# geekworm-monitor.net
KiCad netlist of a schematic drawn in EAGLE
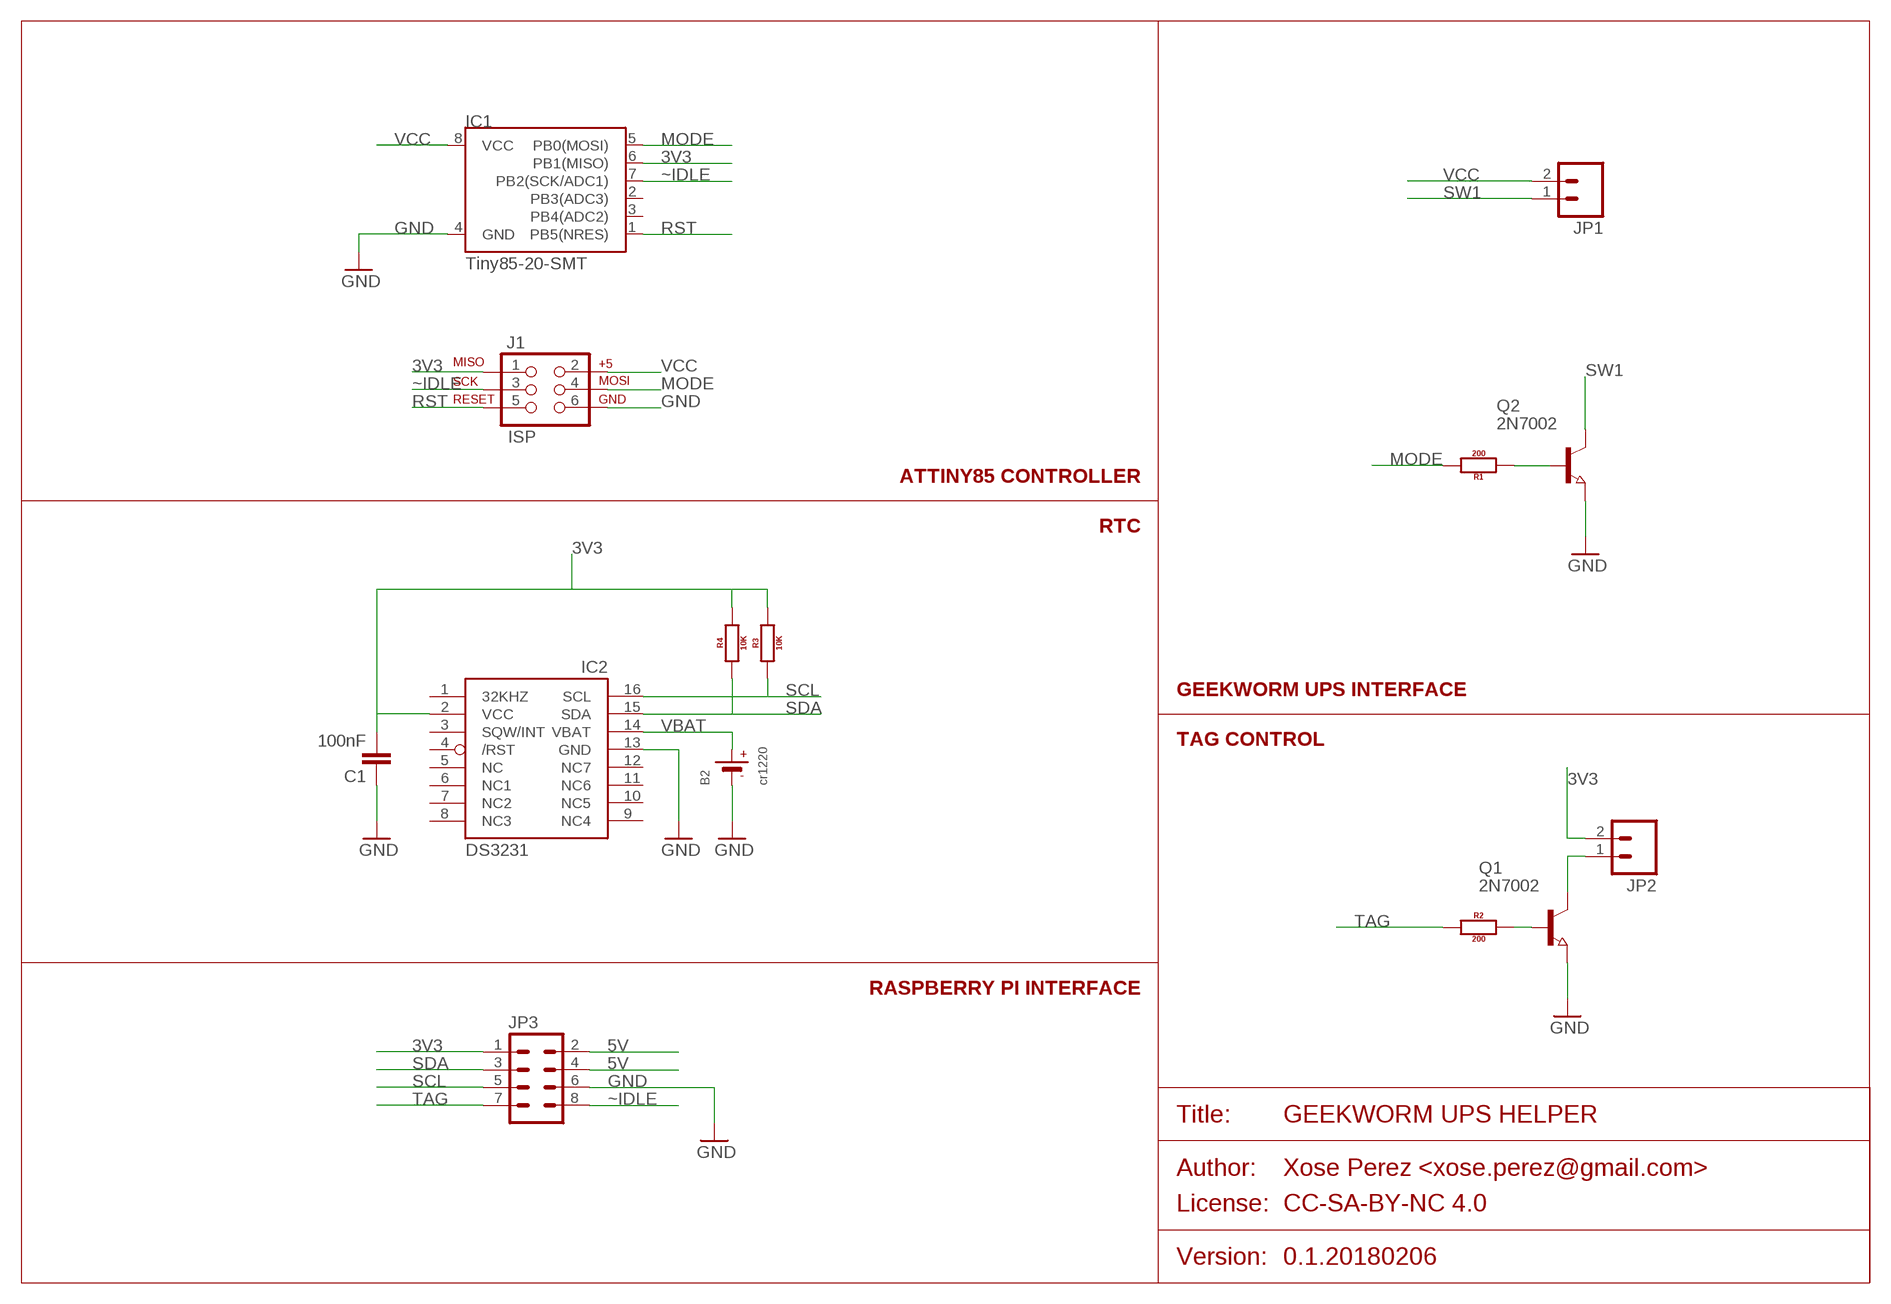
[diagram p0: schematic, sheet 1]

(export (version "E")
  (design (tool "Eeschema 10.0.6"))
  (components
    (comp (ref "B2")
      (value "cr1220")
      (footprint "eagle-import:MICROBUILDER_CR1220-2")
      (libsource (lib "eagle-import") (part "MICROBUILDER_BATTERYCR1220_2"))
    )
    (comp (ref "C1")
      (value "100nF")
      (footprint "eagle-import:0805")
      (libsource (lib "eagle-import") (part "C-EU0805"))
    )
    (comp (ref "IC1")
      (value "Tiny85-20-SMT")
      (footprint "eagle-import:SO08-EIAJ")
      (libsource (lib "eagle-import") (part "ATTINY45TINY85-20-SMT"))
    )
    (comp (ref "IC2")
      (value "DS3231/SO")
      (footprint "eagle-import:SO16W")
      (libsource (lib "eagle-import") (part "DS3231/SO"))
    )
    (comp (ref "J1")
      (value "ISP")
      (footprint "eagle-import:2X3EDGE")
      (libsource (lib "eagle-import") (part "AVR_SPIEDGE"))
    )
    (comp (ref "JP1")
      (value "M02-JST-2MM-SMT")
      (footprint "eagle-import:JST-2-SMD")
      (libsource (lib "eagle-import") (part "M02-JST-2MM-SMT"))
    )
    (comp (ref "JP2")
      (value "M02-JST-2MM-SMT")
      (footprint "eagle-import:JST-2-SMD")
      (libsource (lib "eagle-import") (part "M02-JST-2MM-SMT"))
    )
    (comp (ref "JP3")
      (value "M04X2")
      (footprint "eagle-import:2X4")
      (libsource (lib "eagle-import") (part "M04X2"))
    )
    (comp (ref "Q1")
      (value "2N7002")
      (footprint "eagle-import:SOT23")
      (libsource (lib "eagle-import") (part "NPN-TRANSISTOR_SOT23"))
    )
    (comp (ref "Q2")
      (value "2N7002")
      (footprint "eagle-import:SOT23")
      (libsource (lib "eagle-import") (part "NPN-TRANSISTOR_SOT23"))
    )
    (comp (ref "R1")
      (value "200")
      (footprint "eagle-import:0805")
      (libsource (lib "eagle-import") (part "RESISTOR0805"))
    )
    (comp (ref "R2")
      (value "200")
      (footprint "eagle-import:0805")
      (libsource (lib "eagle-import") (part "RESISTOR0805"))
    )
    (comp (ref "R3")
      (value "10K")
      (footprint "eagle-import:0805")
      (libsource (lib "eagle-import") (part "RESISTOR0805"))
    )
    (comp (ref "R4")
      (value "10K")
      (footprint "eagle-import:0805")
      (libsource (lib "eagle-import") (part "RESISTOR0805"))
    )
  )
  (nets
    (net (code "1") (name "/3V3") (class "Default")
      (node (ref "C1") (pin "2") (pinfunction "2_2") (pintype "passive"))
      (node (ref "IC1") (pin "6") (pinfunction "PB1(MISO)_6") (pintype "bidirectional"))
      (node (ref "IC2") (pin "2") (pinfunction "VCC_2") (pintype "power_in"))
      (node (ref "J1") (pin "1") (pinfunction "1_1") (pintype "passive"))
      (node (ref "JP2") (pin "2") (pinfunction "1_2") (pintype "passive"))
      (node (ref "JP3") (pin "1") (pinfunction "1_1") (pintype "passive"))
      (node (ref "R3") (pin "2") (pinfunction "2_2") (pintype "passive"))
      (node (ref "R4") (pin "2") (pinfunction "2_2") (pintype "passive"))
    )
    (net (code "2") (name "/5V") (class "Default")
      (node (ref "JP3") (pin "2") (pinfunction "2_2") (pintype "passive"))
      (node (ref "JP3") (pin "4") (pinfunction "4_4") (pintype "passive"))
    )
    (net (code "3") (name "/MODE") (class "Default")
      (node (ref "IC1") (pin "5") (pinfunction "PB0(MOSI)_5") (pintype "bidirectional"))
      (node (ref "J1") (pin "4") (pinfunction "4_4") (pintype "passive"))
      (node (ref "R1") (pin "2") (pinfunction "2_2") (pintype "passive"))
    )
    (net (code "4") (name "/RST") (class "Default")
      (node (ref "IC1") (pin "1") (pinfunction "PB5(NRES)_1") (pintype "bidirectional"))
      (node (ref "J1") (pin "5") (pinfunction "5_5") (pintype "passive"))
    )
    (net (code "5") (name "/SCL") (class "Default")
      (node (ref "IC2") (pin "16") (pinfunction "SCL_16") (pintype "bidirectional"))
      (node (ref "JP3") (pin "5") (pinfunction "5_5") (pintype "passive"))
      (node (ref "R3") (pin "1") (pinfunction "1_1") (pintype "passive"))
    )
    (net (code "6") (name "/SDA") (class "Default")
      (node (ref "IC2") (pin "15") (pinfunction "SDA_15") (pintype "bidirectional"))
      (node (ref "JP3") (pin "3") (pinfunction "3_3") (pintype "passive"))
      (node (ref "R4") (pin "1") (pinfunction "1_1") (pintype "passive"))
    )
    (net (code "7") (name "/SW1") (class "Default")
      (node (ref "JP1") (pin "1") (pinfunction "2_1") (pintype "passive"))
      (node (ref "Q2") (pin "3") (pinfunction "C_3") (pintype "passive"))
    )
    (net (code "8") (name "/TAG") (class "Default")
      (node (ref "JP3") (pin "7") (pinfunction "7_7") (pintype "passive"))
      (node (ref "R2") (pin "1") (pinfunction "1_1") (pintype "passive"))
    )
    (net (code "9") (name "/VBAT") (class "Default")
      (node (ref "B2") (pin "+") (pinfunction "+_+") (pintype "passive"))
      (node (ref "IC2") (pin "14") (pinfunction "VBAT_14") (pintype "power_in"))
    )
    (net (code "10") (name "/VCC") (class "Default")
      (node (ref "IC1") (pin "8") (pinfunction "VCC_8") (pintype "bidirectional"))
      (node (ref "J1") (pin "2") (pinfunction "2_2") (pintype "passive"))
      (node (ref "JP1") (pin "2") (pinfunction "1_2") (pintype "passive"))
    )
    (net (code "11") (name "/~{IDLE}") (class "Default")
      (node (ref "IC1") (pin "7") (pinfunction "PB2(SCK/ADC1)_7") (pintype "bidirectional"))
      (node (ref "J1") (pin "3") (pinfunction "3_3") (pintype "passive"))
      (node (ref "JP3") (pin "8") (pinfunction "8_8") (pintype "passive"))
    )
    (net (code "12") (name "GND") (class "Default")
      (node (ref "B2") (pin "-") (pinfunction "-_-") (pintype "passive"))
      (node (ref "C1") (pin "1") (pinfunction "1_1") (pintype "passive"))
      (node (ref "IC1") (pin "4") (pinfunction "GND_4") (pintype "bidirectional"))
      (node (ref "IC2") (pin "13") (pinfunction "GND_13") (pintype "power_in"))
      (node (ref "J1") (pin "6") (pinfunction "6_6") (pintype "passive"))
      (node (ref "JP3") (pin "6") (pinfunction "6_6") (pintype "passive"))
      (node (ref "Q1") (pin "2") (pinfunction "E_2") (pintype "passive"))
      (node (ref "Q2") (pin "2") (pinfunction "E_2") (pintype "passive"))
    )
    (net (code "13") (name "Net-(JP2-2)") (class "Default")
      (node (ref "JP2") (pin "1") (pinfunction "2_1") (pintype "passive"))
      (node (ref "Q1") (pin "3") (pinfunction "C_3") (pintype "passive"))
    )
    (net (code "14") (name "Net-(Q1-B)") (class "Default")
      (node (ref "Q1") (pin "1") (pinfunction "B_1") (pintype "passive"))
      (node (ref "R2") (pin "2") (pinfunction "2_2") (pintype "passive"))
    )
    (net (code "15") (name "Net-(Q2-B)") (class "Default")
      (node (ref "Q2") (pin "1") (pinfunction "B_1") (pintype "passive"))
      (node (ref "R1") (pin "1") (pinfunction "1_1") (pintype "passive"))
    )
    (net (code "16") (name "unconnected-(IC1-PB3(ADC3)-Pad2)") (class "Default")
      (node (ref "IC1") (pin "2") (pinfunction "PB3(ADC3)_2") (pintype "bidirectional"))
    )
    (net (code "17") (name "unconnected-(IC1-PB4(ADC2)-Pad3)") (class "Default")
      (node (ref "IC1") (pin "3") (pinfunction "PB4(ADC2)_3") (pintype "bidirectional"))
    )
    (net (code "18") (name "unconnected-(IC2-32KHZ-Pad1)") (class "Default")
      (node (ref "IC2") (pin "1") (pinfunction "32KHZ_1") (pintype "output"))
    )
    (net (code "19") (name "unconnected-(IC2-NC-Pad5)") (class "Default")
      (node (ref "IC2") (pin "5") (pinfunction "NC_5") (pintype "no_connect"))
    )
    (net (code "20") (name "unconnected-(IC2-NC1-Pad6)") (class "Default")
      (node (ref "IC2") (pin "6") (pinfunction "NC1_6") (pintype "no_connect"))
    )
    (net (code "21") (name "unconnected-(IC2-NC2-Pad7)") (class "Default")
      (node (ref "IC2") (pin "7") (pinfunction "NC2_7") (pintype "no_connect"))
    )
    (net (code "22") (name "unconnected-(IC2-NC3-Pad8)") (class "Default")
      (node (ref "IC2") (pin "8") (pinfunction "NC3_8") (pintype "no_connect"))
    )
    (net (code "23") (name "unconnected-(IC2-NC4-Pad9)") (class "Default")
      (node (ref "IC2") (pin "9") (pinfunction "NC4_9") (pintype "no_connect"))
    )
    (net (code "24") (name "unconnected-(IC2-NC5-Pad10)") (class "Default")
      (node (ref "IC2") (pin "10") (pinfunction "NC5_10") (pintype "no_connect"))
    )
    (net (code "25") (name "unconnected-(IC2-NC6-Pad11)") (class "Default")
      (node (ref "IC2") (pin "11") (pinfunction "NC6_11") (pintype "no_connect"))
    )
    (net (code "26") (name "unconnected-(IC2-NC7-Pad12)") (class "Default")
      (node (ref "IC2") (pin "12") (pinfunction "NC7_12") (pintype "no_connect"))
    )
    (net (code "27") (name "unconnected-(IC2-SQW{slash}INT-Pad3)") (class "Default")
      (node (ref "IC2") (pin "3") (pinfunction "SQW/INT_3") (pintype "output"))
    )
    (net (code "28") (name "unconnected-(IC2-{slash}RST-Pad4)") (class "Default")
      (node (ref "IC2") (pin "4") (pinfunction "/RST_4") (pintype "passive"))
    )
  )
)
